# analyzer.net
KiCad netlist of a schematic drawn in EAGLE
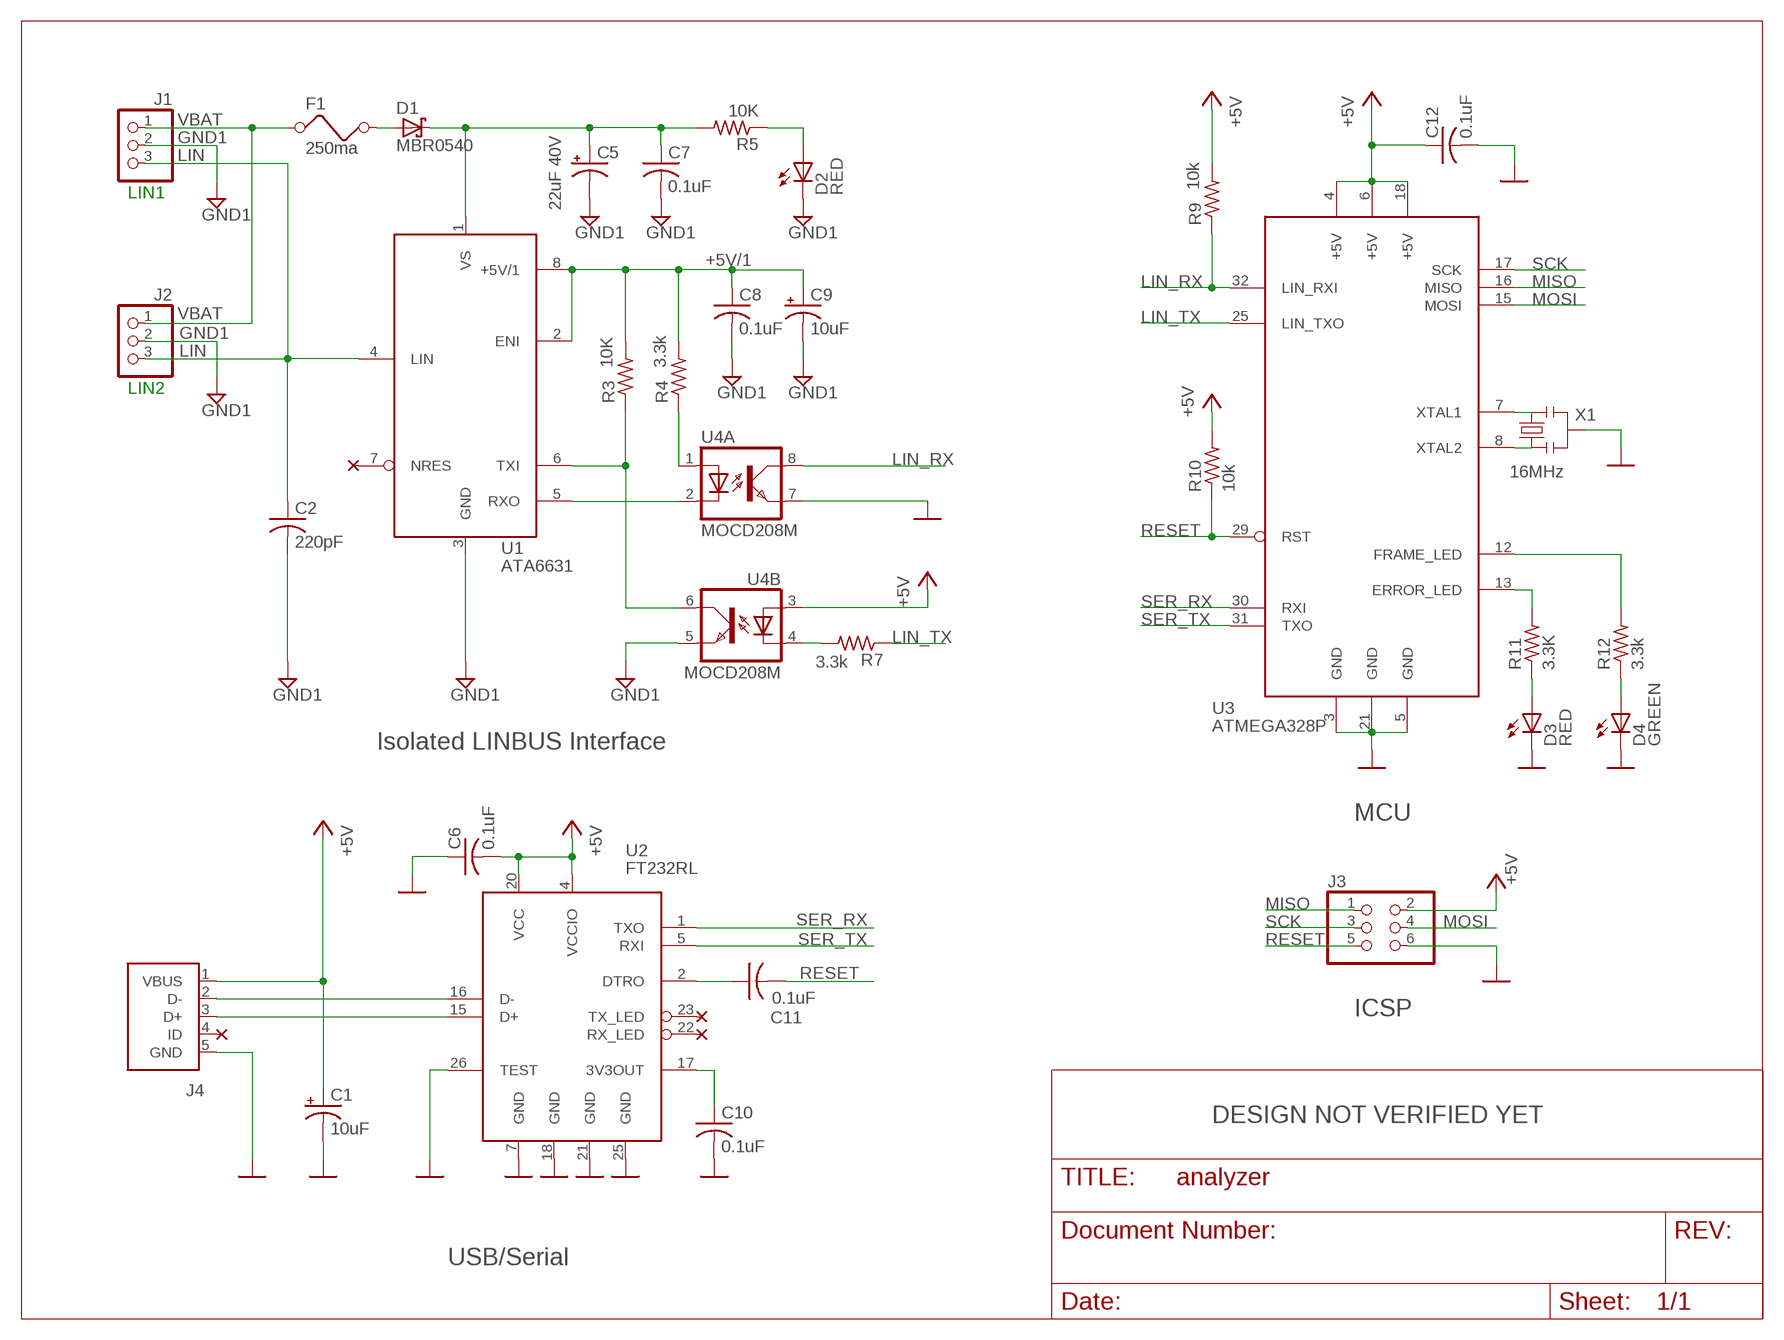
[diagram p0: schematic, sheet 1]

(export (version "E")
  (design (tool "Eeschema 10.0.6"))
  (components
    (comp (ref "C1")
      (value "10uF")
      (footprint "eagle-import:A_3216-18R")
      (libsource (lib "eagle-import") (part "CPOL-USA/3216-18R"))
    )
    (comp (ref "C2")
      (value "220pF")
      (footprint "eagle-import:C0805")
      (libsource (lib "eagle-import") (part "C-USC0805"))
    )
    (comp (ref "C5")
      (value "22uF 40V")
      (footprint "eagle-import:UD-6,3X5,8_NICHICON")
      (libsource (lib "eagle-import") (part "CPOL-USUD-6,3X5,8"))
    )
    (comp (ref "C6")
      (value "0.1uF")
      (footprint "eagle-import:C0805")
      (libsource (lib "eagle-import") (part "C-USC0805"))
    )
    (comp (ref "C7")
      (value "0.1uF")
      (footprint "eagle-import:C0805")
      (libsource (lib "eagle-import") (part "C-USC0805"))
    )
    (comp (ref "C8")
      (value "0.1uF")
      (footprint "eagle-import:C0805")
      (libsource (lib "eagle-import") (part "C-USC0805"))
    )
    (comp (ref "C9")
      (value "10uF")
      (footprint "eagle-import:A_3216-18R")
      (libsource (lib "eagle-import") (part "CPOL-USA/3216-18R"))
    )
    (comp (ref "C10")
      (value "0.1uF")
      (footprint "eagle-import:C0805")
      (libsource (lib "eagle-import") (part "C-USC0805"))
    )
    (comp (ref "C11")
      (value "0.1uF")
      (footprint "eagle-import:C0805")
      (libsource (lib "eagle-import") (part "C-USC0805"))
    )
    (comp (ref "C12")
      (value "0.1uF")
      (footprint "eagle-import:C0805")
      (libsource (lib "eagle-import") (part "C-USC0805"))
    )
    (comp (ref "D1")
      (value "MBR0540")
      (footprint "eagle-import:SOD123FL")
      (libsource (lib "eagle-import") (part "SMF5.0AT1"))
    )
    (comp (ref "D2")
      (value "RED")
      (footprint "eagle-import:1206")
      (libsource (lib "eagle-import") (part "LEDSMT1206"))
    )
    (comp (ref "D3")
      (value "RED")
      (footprint "eagle-import:1206")
      (libsource (lib "eagle-import") (part "LEDSMT1206"))
    )
    (comp (ref "D4")
      (value "GREEN")
      (footprint "eagle-import:1206")
      (libsource (lib "eagle-import") (part "LEDSMT1206"))
    )
    (comp (ref "F1")
      (value "250ma")
      (footprint "eagle-import:1206")
      (libsource (lib "eagle-import") (part "FUSE"))
    )
    (comp (ref "J1")
      (value "PINHD-1X3")
      (footprint "eagle-import:1X03")
      (libsource (lib "eagle-import") (part "PINHD-1X3"))
    )
    (comp (ref "J2")
      (value "PINHD-1X3")
      (footprint "eagle-import:1X03")
      (libsource (lib "eagle-import") (part "PINHD-1X3"))
    )
    (comp (ref "J3")
      (value "PINHD-2X3")
      (footprint "eagle-import:2X03")
      (libsource (lib "eagle-import") (part "PINHD-2X3"))
    )
    (comp (ref "J4")
      (value "USBSMD")
      (footprint "eagle-import:USB-MINIB")
      (libsource (lib "eagle-import") (part "USBSMD"))
    )
    (comp (ref "R3")
      (value "10K")
      (footprint "eagle-import:R0805")
      (libsource (lib "eagle-import") (part "R-US_R0805"))
    )
    (comp (ref "R4")
      (value "3.3k")
      (footprint "eagle-import:R0805")
      (libsource (lib "eagle-import") (part "R-US_R0805"))
    )
    (comp (ref "R5")
      (value "10K")
      (footprint "eagle-import:R0805")
      (libsource (lib "eagle-import") (part "R-US_R0805"))
    )
    (comp (ref "R7")
      (value "3.3k")
      (footprint "eagle-import:R0805")
      (libsource (lib "eagle-import") (part "R-US_R0805"))
    )
    (comp (ref "R9")
      (value "10k")
      (footprint "eagle-import:R0805")
      (libsource (lib "eagle-import") (part "R-US_R0805"))
    )
    (comp (ref "R10")
      (value "10k")
      (footprint "eagle-import:R0805")
      (libsource (lib "eagle-import") (part "R-US_R0805"))
    )
    (comp (ref "R11")
      (value "3.3K")
      (footprint "eagle-import:R0805")
      (libsource (lib "eagle-import") (part "R-US_R0805"))
    )
    (comp (ref "R12")
      (value "3.3k")
      (footprint "eagle-import:R0805")
      (libsource (lib "eagle-import") (part "R-US_R0805"))
    )
    (comp (ref "U1")
      (value "ATA6631")
      (footprint "eagle-import:SO-08")
      (libsource (lib "eagle-import") (part "ATA6631"))
    )
    (comp (ref "U2")
      (value "FT232RL")
      (footprint "eagle-import:SSOP28DB")
      (libsource (lib "eagle-import") (part "FT232RL"))
    )
    (comp (ref "U3")
      (value "ATMEGA328P")
      (footprint "eagle-import:TQFP32-08")
      (libsource (lib "eagle-import") (part "ATMEGA328P"))
    )
    (comp (ref "U4")
      (value "MOCD208M")
      (footprint "eagle-import:SOIC08-FAIRCHILD")
      (fields (field (name "MF") "FAIRCHILD SEMICONDUCTOR"))
      (libsource (lib "eagle-import") (part "MOCD20M8"))
    )
    (comp (ref "X1")
      (value "16MHz")
      (footprint "eagle-import:RESONATOR-SMD")
      (libsource (lib "eagle-import") (part "RESONATORSMD"))
    )
  )
  (nets
    (net (code "1") (name "+5V") (class "Default")
      (node (ref "C1") (pin "+") (pinfunction "+_+") (pintype "passive"))
      (node (ref "C12") (pin "1") (pinfunction "1_1") (pintype "passive"))
      (node (ref "C6") (pin "2") (pinfunction "2_2") (pintype "passive"))
      (node (ref "J3") (pin "2") (pinfunction "2_2") (pintype "passive"))
      (node (ref "J4") (pin "1") (pinfunction "VBUS_1") (pintype "bidirectional"))
      (node (ref "R10") (pin "2") (pinfunction "2_2") (pintype "passive"))
      (node (ref "R9") (pin "2") (pinfunction "2_2") (pintype "passive"))
      (node (ref "U2") (pin "20") (pinfunction "VCC_20") (pintype "power_in"))
      (node (ref "U2") (pin "4") (pinfunction "VCCIO_4") (pintype "power_in"))
      (node (ref "U3") (pin "18") (pinfunction "+5V_18") (pintype "power_in"))
      (node (ref "U3") (pin "4") (pinfunction "+5V_4") (pintype "power_in"))
      (node (ref "U3") (pin "6") (pinfunction "+5V_6") (pintype "power_in"))
      (node (ref "U4") (pin "3") (pinfunction "A_3") (pintype "passive"))
    )
    (net (code "2") (name "/+5V{slash}1") (class "Default")
      (node (ref "C8") (pin "1") (pinfunction "1_1") (pintype "passive"))
      (node (ref "C9") (pin "+") (pinfunction "+_+") (pintype "passive"))
      (node (ref "R3") (pin "2") (pinfunction "2_2") (pintype "passive"))
      (node (ref "R4") (pin "2") (pinfunction "2_2") (pintype "passive"))
      (node (ref "U1") (pin "2") (pinfunction "ENI_2") (pintype "input"))
      (node (ref "U1") (pin "8") (pinfunction "+5V/1_8") (pintype "power_in"))
    )
    (net (code "3") (name "/LIN") (class "Default")
      (node (ref "C2") (pin "1") (pinfunction "1_1") (pintype "passive"))
      (node (ref "J1") (pin "3") (pinfunction "3_3") (pintype "passive"))
      (node (ref "J2") (pin "3") (pinfunction "3_3") (pintype "passive"))
      (node (ref "U1") (pin "4") (pinfunction "LIN_4") (pintype "bidirectional"))
    )
    (net (code "4") (name "/LIN_RX") (class "Default")
      (node (ref "R9") (pin "1") (pinfunction "1_1") (pintype "passive"))
      (node (ref "U3") (pin "32") (pinfunction "LIN_RXI_32") (pintype "input"))
      (node (ref "U4") (pin "8") (pinfunction "COL_8") (pintype "passive"))
    )
    (net (code "5") (name "/LIN_TX") (class "Default")
      (node (ref "R7") (pin "1") (pinfunction "1_1") (pintype "passive"))
      (node (ref "U3") (pin "25") (pinfunction "LIN_TXO_25") (pintype "output"))
    )
    (net (code "6") (name "/MISO") (class "Default")
      (node (ref "J3") (pin "1") (pinfunction "1_1") (pintype "passive"))
      (node (ref "U3") (pin "16") (pinfunction "MISO_16") (pintype "input"))
    )
    (net (code "7") (name "/MOSI") (class "Default")
      (node (ref "J3") (pin "4") (pinfunction "4_4") (pintype "passive"))
      (node (ref "U3") (pin "15") (pinfunction "MOSI_15") (pintype "input"))
    )
    (net (code "8") (name "/RESET") (class "Default")
      (node (ref "C11") (pin "2") (pinfunction "2_2") (pintype "passive"))
      (node (ref "J3") (pin "5") (pinfunction "5_5") (pintype "passive"))
      (node (ref "R10") (pin "1") (pinfunction "1_1") (pintype "passive"))
      (node (ref "U3") (pin "29") (pinfunction "RST_29") (pintype "input"))
    )
    (net (code "9") (name "/SCK") (class "Default")
      (node (ref "J3") (pin "3") (pinfunction "3_3") (pintype "passive"))
      (node (ref "U3") (pin "17") (pinfunction "SCK_17") (pintype "output"))
    )
    (net (code "10") (name "/SER_RX") (class "Default")
      (node (ref "U2") (pin "1") (pinfunction "TXO_1") (pintype "output"))
      (node (ref "U3") (pin "30") (pinfunction "RXI_30") (pintype "input"))
    )
    (net (code "11") (name "/SER_TX") (class "Default")
      (node (ref "U2") (pin "5") (pinfunction "RXI_5") (pintype "input"))
      (node (ref "U3") (pin "31") (pinfunction "TXO_31") (pintype "output"))
    )
    (net (code "12") (name "/VBAT") (class "Default")
      (node (ref "F1") (pin "1") (pinfunction "1_1") (pintype "passive"))
      (node (ref "J1") (pin "1") (pinfunction "1_1") (pintype "passive"))
      (node (ref "J2") (pin "1") (pinfunction "1_1") (pintype "passive"))
    )
    (net (code "13") (name "GND") (class "Default")
      (node (ref "C1") (pin "-") (pinfunction "-_-") (pintype "passive"))
      (node (ref "C10") (pin "2") (pinfunction "2_2") (pintype "passive"))
      (node (ref "C12") (pin "2") (pinfunction "2_2") (pintype "passive"))
      (node (ref "C6") (pin "1") (pinfunction "1_1") (pintype "passive"))
      (node (ref "D3") (pin "C") (pinfunction "C_C") (pintype "passive"))
      (node (ref "D4") (pin "C") (pinfunction "C_C") (pintype "passive"))
      (node (ref "J3") (pin "6") (pinfunction "6_6") (pintype "passive"))
      (node (ref "J4") (pin "5") (pinfunction "GND_5") (pintype "bidirectional"))
      (node (ref "U2") (pin "18") (pinfunction "GND_18") (pintype "power_in"))
      (node (ref "U2") (pin "21") (pinfunction "GND_21") (pintype "power_in"))
      (node (ref "U2") (pin "25") (pinfunction "GND_25") (pintype "power_in"))
      (node (ref "U2") (pin "26") (pinfunction "TEST_26") (pintype "input"))
      (node (ref "U2") (pin "7") (pinfunction "GND_7") (pintype "power_in"))
      (node (ref "U3") (pin "21") (pinfunction "GND_21") (pintype "power_in"))
      (node (ref "U3") (pin "3") (pinfunction "GND_3") (pintype "power_in"))
      (node (ref "U3") (pin "5") (pinfunction "GND_5") (pintype "power_in"))
      (node (ref "U4") (pin "7") (pinfunction "EMIT_7") (pintype "passive"))
      (node (ref "X1") (pin "2") (pinfunction "2_2") (pintype "passive"))
    )
    (net (code "14") (name "GND1") (class "Default")
      (node (ref "C2") (pin "2") (pinfunction "2_2") (pintype "passive"))
      (node (ref "C5") (pin "-") (pinfunction "-_-") (pintype "passive"))
      (node (ref "C7") (pin "2") (pinfunction "2_2") (pintype "passive"))
      (node (ref "C8") (pin "2") (pinfunction "2_2") (pintype "passive"))
      (node (ref "C9") (pin "-") (pinfunction "-_-") (pintype "passive"))
      (node (ref "D2") (pin "C") (pinfunction "C_C") (pintype "passive"))
      (node (ref "J1") (pin "2") (pinfunction "2_2") (pintype "passive"))
      (node (ref "J2") (pin "2") (pinfunction "2_2") (pintype "passive"))
      (node (ref "U1") (pin "3") (pinfunction "GND_3") (pintype "power_in"))
      (node (ref "U4") (pin "5") (pinfunction "EMIT_5") (pintype "passive"))
    )
    (net (code "15") (name "Net-(D1-PadA)") (class "Default")
      (node (ref "D1") (pin "A") (pinfunction "A_A") (pintype "passive"))
      (node (ref "F1") (pin "2") (pinfunction "2_2") (pintype "passive"))
    )
    (net (code "16") (name "Net-(D2-PadA)") (class "Default")
      (node (ref "D2") (pin "A") (pinfunction "A_A") (pintype "passive"))
      (node (ref "R5") (pin "1") (pinfunction "1_1") (pintype "passive"))
    )
    (net (code "17") (name "Net-(D3-PadA)") (class "Default")
      (node (ref "D3") (pin "A") (pinfunction "A_A") (pintype "passive"))
      (node (ref "R11") (pin "1") (pinfunction "1_1") (pintype "passive"))
    )
    (net (code "18") (name "Net-(D4-PadA)") (class "Default")
      (node (ref "D4") (pin "A") (pinfunction "A_A") (pintype "passive"))
      (node (ref "R12") (pin "1") (pinfunction "1_1") (pintype "passive"))
    )
    (net (code "19") (name "Net-(J4-D+)") (class "Default")
      (node (ref "J4") (pin "3") (pinfunction "D+_3") (pintype "bidirectional"))
      (node (ref "U2") (pin "15") (pinfunction "D+_15") (pintype "passive"))
    )
    (net (code "20") (name "Net-(J4-D-)") (class "Default")
      (node (ref "J4") (pin "2") (pinfunction "D-_2") (pintype "bidirectional"))
      (node (ref "U2") (pin "16") (pinfunction "D-_16") (pintype "passive"))
    )
    (net (code "21") (name "Net-(U1-RXO)") (class "Default")
      (node (ref "U1") (pin "5") (pinfunction "RXO_5") (pintype "output"))
      (node (ref "U4") (pin "2") (pinfunction "C_2") (pintype "passive"))
    )
    (net (code "22") (name "Net-(U1-TXI)") (class "Default")
      (node (ref "R3") (pin "1") (pinfunction "1_1") (pintype "passive"))
      (node (ref "U1") (pin "6") (pinfunction "TXI_6") (pintype "input"))
      (node (ref "U4") (pin "6") (pinfunction "COL_6") (pintype "passive"))
    )
    (net (code "23") (name "Net-(U1-VS)") (class "Default")
      (node (ref "C5") (pin "+") (pinfunction "+_+") (pintype "passive"))
      (node (ref "C7") (pin "1") (pinfunction "1_1") (pintype "passive"))
      (node (ref "D1") (pin "C") (pinfunction "C_C") (pintype "passive"))
      (node (ref "R5") (pin "2") (pinfunction "2_2") (pintype "passive"))
      (node (ref "U1") (pin "1") (pinfunction "VS_1") (pintype "power_in"))
    )
    (net (code "24") (name "Net-(U2-3V3OUT)") (class "Default")
      (node (ref "C10") (pin "1") (pinfunction "1_1") (pintype "passive"))
      (node (ref "U2") (pin "17") (pinfunction "3V3OUT_17") (pintype "power_in"))
    )
    (net (code "25") (name "Net-(U2-DTRO)") (class "Default")
      (node (ref "C11") (pin "1") (pinfunction "1_1") (pintype "passive"))
      (node (ref "U2") (pin "2") (pinfunction "DTRO_2") (pintype "output"))
    )
    (net (code "26") (name "Net-(U3-ERROR_LED)") (class "Default")
      (node (ref "R11") (pin "2") (pinfunction "2_2") (pintype "passive"))
      (node (ref "U3") (pin "13") (pinfunction "ERROR_LED_13") (pintype "output"))
    )
    (net (code "27") (name "Net-(U3-FRAME_LED)") (class "Default")
      (node (ref "R12") (pin "2") (pinfunction "2_2") (pintype "passive"))
      (node (ref "U3") (pin "12") (pinfunction "FRAME_LED_12") (pintype "output"))
    )
    (net (code "28") (name "Net-(U3-XTAL1)") (class "Default")
      (node (ref "U3") (pin "7") (pinfunction "XTAL1_7") (pintype "passive"))
      (node (ref "X1") (pin "3") (pinfunction "3_3") (pintype "passive"))
    )
    (net (code "29") (name "Net-(U3-XTAL2)") (class "Default")
      (node (ref "U3") (pin "8") (pinfunction "XTAL2_8") (pintype "passive"))
      (node (ref "X1") (pin "1") (pinfunction "1_1") (pintype "passive"))
    )
    (net (code "30") (name "Net-(U4A-A)") (class "Default")
      (node (ref "R4") (pin "1") (pinfunction "1_1") (pintype "passive"))
      (node (ref "U4") (pin "1") (pinfunction "A_1") (pintype "passive"))
    )
    (net (code "31") (name "Net-(U4B-C)") (class "Default")
      (node (ref "R7") (pin "2") (pinfunction "2_2") (pintype "passive"))
      (node (ref "U4") (pin "4") (pinfunction "C_4") (pintype "passive"))
    )
    (net (code "32") (name "unconnected-(J4-ID-Pad4)") (class "Default")
      (node (ref "J4") (pin "4") (pinfunction "ID_4") (pintype "bidirectional"))
    )
    (net (code "33") (name "unconnected-(U1-NRES-Pad7)") (class "Default")
      (node (ref "U1") (pin "7") (pinfunction "NRES_7") (pintype "output"))
    )
    (net (code "34") (name "unconnected-(U2-RX_LED-Pad22)") (class "Default")
      (node (ref "U2") (pin "22") (pinfunction "RX_LED_22") (pintype "output"))
    )
    (net (code "35") (name "unconnected-(U2-TX_LED-Pad23)") (class "Default")
      (node (ref "U2") (pin "23") (pinfunction "TX_LED_23") (pintype "output"))
    )
  )
)
